# PowerManagement.net
KiCad netlist of a schematic drawn in Altium Designer
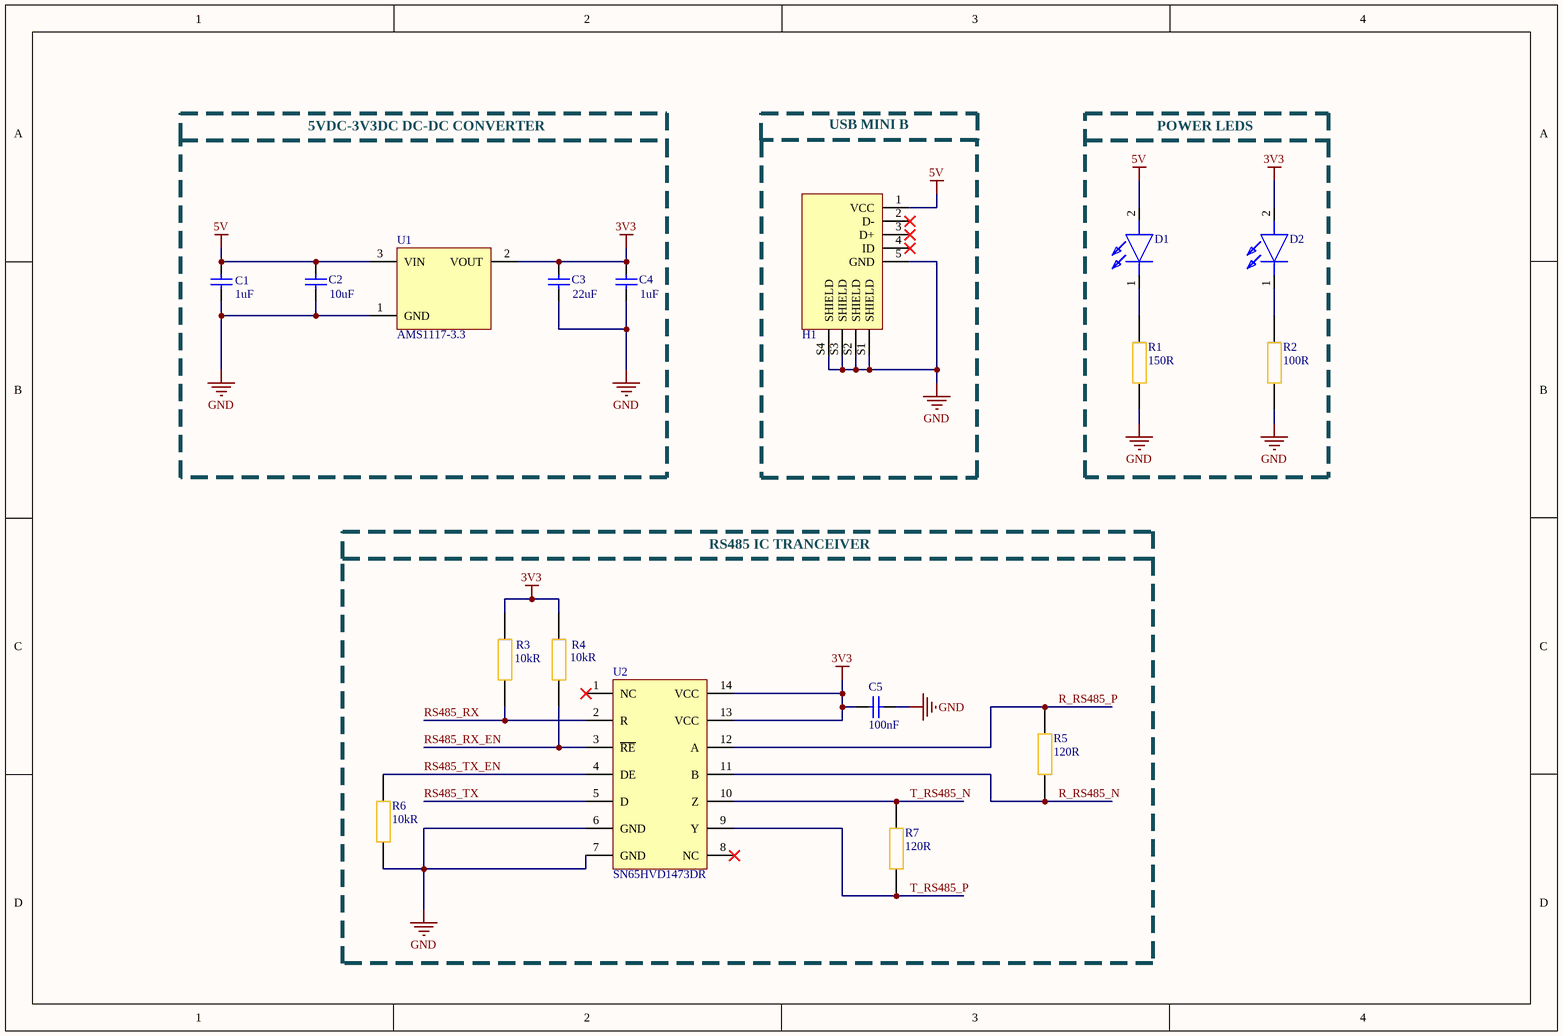
[diagram p0: PowerManagement.SchDoc]

(export (version "E")
  (design (tool "Eeschema 10.0.6"))
  (components
    (comp (ref "C1")
      (value "1uF")
      (footprint "WCAP-CSGP_0603_L1.6W0.8H0.8_Reflow")
      (description "WCAP-CSGP Multilayer Ceramic Chip Capacitor, General Purpose, size 0603, X5R, 1µF, 10VDC")
      (fields
        (field (name "MANUFACTURER PART NUMBER") "885012106010")
        (field (name "MANUFACTURER") "Wurth Elektronik")
        (field (name "CAPACITANCE") "1uF")
      )
      (libsource (lib "WE - Passive Components") (part "Capacitor_Non-Polarized"))
    )
    (comp (ref "C2")
      (value "10uF")
      (footprint "WCAP-CSGP_0603_L1.6W0.8H0.8_Reflow")
      (description "WCAP-CSGP Multilayer Ceramic Chip Capacitor, General Purpose, size 0603, X5R, 10µF, 25VDC")
      (fields
        (field (name "MANUFACTURER PART NUMBER") "885012106031")
        (field (name "MANUFACTURER") "Wurth Elektronik")
        (field (name "CAPACITANCE") "10uF")
      )
      (libsource (lib "WE - Passive Components") (part "Capacitor_Non-Polarized"))
    )
    (comp (ref "C3")
      (value "22uF")
      (footprint "WCAP-CSGP_0805_L2W1.25H1.25")
      (description "WCAP-CSGP Multilayer Ceramic Chip Capacitor, General Purpose, size 0805, X5R, 22µF, 10VDC")
      (fields
        (field (name "MANUFACTURER PART NUMBER") "885012107011")
        (field (name "MANUFACTURER") "Wurth Elektronik")
        (field (name "CAPACITANCE") "22uF")
      )
      (libsource (lib "WE - Passive Components") (part "Capacitor_Non-Polarized"))
    )
    (comp (ref "C4")
      (value "1uF")
      (footprint "WCAP-CSGP_0603_L1.6W0.8H0.8_Reflow")
      (description "WCAP-CSGP Multilayer Ceramic Chip Capacitor, General Purpose, size 0603, X5R, 1µF, 10VDC")
      (fields
        (field (name "MANUFACTURER PART NUMBER") "885012106010")
        (field (name "MANUFACTURER") "Wurth Elektronik")
        (field (name "CAPACITANCE") "1uF")
      )
      (libsource (lib "WE - Passive Components") (part "Capacitor_Non-Polarized"))
    )
    (comp (ref "C5")
      (value "100nF")
      (footprint "WCAP-CSGP_0603_L1.6W0.8H0.8_Reflow")
      (description "WCAP-CSGP Multilayer Ceramic Chip Capacitor, General Purpose, size 0603, X7R, 100nF, 16VDC")
      (fields
        (field (name "MANUFACTURER PART NUMBER") "885012206046")
        (field (name "MANUFACTURER") "Wurth Elektronik")
      )
      (libsource (lib "WE - Passive Components") (part "Capacitor_Non-Polarized"))
    )
    (comp (ref "D1")
      (value "APT1608SGC")
      (footprint "LED GREEN")
      (description "LED GREEN CLEAR 0603 SMD")
      (fields (field (name "MANUFACTURER") "Kingbright") (field (name "DESIGNED BY") "ADAK"))
      (libsource (lib "Integrated_Library5") (part "APT1608SGC"))
    )
    (comp (ref "D2")
      (value "APT1608SGC")
      (footprint "LED GREEN")
      (description "LED GREEN CLEAR 0603 SMD")
      (fields (field (name "MANUFACTURER") "Kingbright") (field (name "DESIGNED BY") "ADAK"))
      (libsource (lib "Integrated_Library5") (part "APT1608SGC"))
    )
    (comp (ref "H1")
      (value "690-005-299-043")
      (footprint "USB")
      (description "CONN RCPT USB2.0 MINI B SMD R/A")
      (fields (field (name "MANUFACTURER") "EDAC") (field (name "DESIGNED BY") "ADAK"))
      (libsource (lib "Integrated_Library5") (part "USB Mini B"))
    )
    (comp (ref "R1")
      (value "RC0603FR-07150RL")
      (footprint "RES 0603")
      (description "RES 150 OHM 1% 1/10W 0603 SMD")
      (fields
        (field (name "MANUFACTURER") "Yageo")
        (field (name "TOLERANCE") "1%")
        (field (name "RESISTANCE") "150R")
        (field (name "DESIGNED BY") "ADAK")
      )
      (libsource (lib "ADAK_Resistors") (part "RES 150 OHM 0603"))
    )
    (comp (ref "R2")
      (value "RC0603FR-13100RL")
      (footprint "RES 0603")
      (description "RES 100 OHM 1% 1/10W 0603 SMD")
      (fields
        (field (name "MANUFACTURER") "Yageo")
        (field (name "TOLERANCE") "1%")
        (field (name "RESISTANCE") "100R")
        (field (name "DESIGNED BY") "ADAK")
      )
      (libsource (lib "ADAK_Resistors") (part "RES 100 OHM 0603"))
    )
    (comp (ref "R3")
      (value "RC0603FR-0710KP")
      (footprint "RES 0603")
      (description "RES 10K OHM 1% 1/10W 0603 SMD")
      (fields
        (field (name "MANUFACTURER") "Yageo")
        (field (name "TOLERANCE") "1%")
        (field (name "RESISTANCE") "10kR")
        (field (name "DESIGNED BY") "ADAK")
      )
      (libsource (lib "ADAK_Resistors") (part "RES 10K OHM 0603"))
    )
    (comp (ref "R4")
      (value "RC0603FR-0710KP")
      (footprint "RES 0603")
      (description "RES 10K OHM 1% 1/10W 0603 SMD")
      (fields
        (field (name "MANUFACTURER") "Yageo")
        (field (name "TOLERANCE") "1%")
        (field (name "RESISTANCE") "10kR")
        (field (name "DESIGNED BY") "ADAK")
      )
      (libsource (lib "ADAK_Resistors") (part "RES 10K OHM 0603"))
    )
    (comp (ref "R5")
      (value "RC0603FR-07120RL")
      (footprint "RES 0603")
      (description "RES 120 OHM 1% 1/10W 0603 SMD")
      (fields
        (field (name "MANUFACTURER") "Yageo")
        (field (name "TOLERANCE") "1%")
        (field (name "RESISTANCE") "120R")
        (field (name "DESIGNED BY") "ADAK")
      )
      (libsource (lib "ADAK_Resistors") (part "RES 120 OHM 0603"))
    )
    (comp (ref "R6")
      (value "RC0603FR-0710KP")
      (footprint "RES 0603")
      (description "RES 10K OHM 1% 1/10W 0603 SMD")
      (fields
        (field (name "MANUFACTURER") "Yageo")
        (field (name "TOLERANCE") "1%")
        (field (name "RESISTANCE") "10kR")
        (field (name "DESIGNED BY") "ADAK")
      )
      (libsource (lib "ADAK_Resistors") (part "RES 10K OHM 0603"))
    )
    (comp (ref "R7")
      (value "RC0603FR-07120RL")
      (footprint "RES 0603")
      (description "RES 120 OHM 1% 1/10W 0603 SMD")
      (fields
        (field (name "MANUFACTURER") "Yageo")
        (field (name "TOLERANCE") "1%")
        (field (name "RESISTANCE") "120R")
        (field (name "DESIGNED BY") "ADAK")
      )
      (libsource (lib "ADAK_Resistors") (part "RES 120 OHM 0603"))
    )
    (comp (ref "U1")
      (value "AMS1117-3.3")
      (footprint "SOT-223")
      (description "Low Dropout Voltage Regulatator SOT-223 1A 3.3V")
      (fields (field (name "DESIGNED BY") "ADAK"))
      (libsource (lib "Integrated_Library5") (part "AMS1117-3.3"))
    )
    (comp (ref "U2")
      (value "SN65HVD1473DR")
      (footprint "14-SOIC")
      (description "IC TRANSCEIVER FULL 1/1 14SOIC")
      (fields (field (name "MANUFACTURER") "Texas Instruments") (field (name "DESIGNED BY") "ADAK"))
      (libsource (lib "Integrated_Library5") (part "SN65HVD1473DR"))
    )
  )
  (nets
    (net (code "1") (name "/RS485_RX") (class "Default")
      (node (ref "R3") (pin "1") (pinfunction "1_1") (pintype "passive"))
      (node (ref "U2") (pin "2") (pinfunction "R_2") (pintype "passive"))
    )
    (net (code "2") (name "/RS485_RX_EN") (class "Default")
      (node (ref "R4") (pin "1") (pinfunction "1_1") (pintype "passive"))
      (node (ref "U2") (pin "3") (pinfunction "~{RE}_3") (pintype "passive"))
    )
    (net (code "3") (name "/RS485_TX") (class "Default")
      (node (ref "U2") (pin "5") (pinfunction "D_5") (pintype "passive"))
    )
    (net (code "4") (name "/RS485_TX_EN") (class "Default")
      (node (ref "R6") (pin "1") (pinfunction "1_1") (pintype "passive"))
      (node (ref "U2") (pin "4") (pinfunction "DE_4") (pintype "passive"))
    )
    (net (code "5") (name "/R_RS485_N") (class "Default")
      (node (ref "R5") (pin "2") (pinfunction "2_2") (pintype "passive"))
      (node (ref "U2") (pin "11") (pinfunction "B_11") (pintype "passive"))
    )
    (net (code "6") (name "/R_RS485_P") (class "Default")
      (node (ref "R5") (pin "1") (pinfunction "1_1") (pintype "passive"))
      (node (ref "U2") (pin "12") (pinfunction "A_12") (pintype "passive"))
    )
    (net (code "7") (name "/T_RS485_N") (class "Default")
      (node (ref "R7") (pin "2") (pinfunction "2_2") (pintype "passive"))
      (node (ref "U2") (pin "10") (pinfunction "Z_10") (pintype "passive"))
    )
    (net (code "8") (name "/T_RS485_P") (class "Default")
      (node (ref "R7") (pin "1") (pinfunction "1_1") (pintype "passive"))
      (node (ref "U2") (pin "9") (pinfunction "Y_9") (pintype "passive"))
    )
    (net (code "9") (name "3V3") (class "Default")
      (node (ref "C3") (pin "2") (pinfunction "2_2") (pintype "passive"))
      (node (ref "C4") (pin "2") (pinfunction "2_2") (pintype "passive"))
      (node (ref "C5") (pin "2") (pinfunction "2_2") (pintype "passive"))
      (node (ref "D2") (pin "2") (pinfunction "A_2") (pintype "passive"))
      (node (ref "R3") (pin "2") (pinfunction "2_2") (pintype "passive"))
      (node (ref "R4") (pin "2") (pinfunction "2_2") (pintype "passive"))
      (node (ref "U1") (pin "2") (pinfunction "VOUT_2") (pintype "passive"))
      (node (ref "U2") (pin "13") (pinfunction "VCC_13") (pintype "passive"))
      (node (ref "U2") (pin "14") (pinfunction "VCC_14") (pintype "passive"))
    )
    (net (code "10") (name "5V") (class "Default")
      (node (ref "C1") (pin "2") (pinfunction "2_2") (pintype "passive"))
      (node (ref "C2") (pin "2") (pinfunction "2_2") (pintype "passive"))
      (node (ref "D1") (pin "2") (pinfunction "A_2") (pintype "passive"))
      (node (ref "H1") (pin "1") (pinfunction "VCC_1") (pintype "passive"))
      (node (ref "U1") (pin "3") (pinfunction "VIN_3") (pintype "passive"))
    )
    (net (code "11") (name "GND") (class "Default")
      (node (ref "C1") (pin "1") (pinfunction "1_1") (pintype "passive"))
      (node (ref "C2") (pin "1") (pinfunction "1_1") (pintype "passive"))
      (node (ref "C3") (pin "1") (pinfunction "1_1") (pintype "passive"))
      (node (ref "C4") (pin "1") (pinfunction "1_1") (pintype "passive"))
      (node (ref "C5") (pin "1") (pinfunction "1_1") (pintype "passive"))
      (node (ref "H1") (pin "5") (pinfunction "GND_5") (pintype "passive"))
      (node (ref "H1") (pin "S1") (pinfunction "SHIELD_S1") (pintype "passive"))
      (node (ref "H1") (pin "S2") (pinfunction "SHIELD_S2") (pintype "passive"))
      (node (ref "H1") (pin "S3") (pinfunction "SHIELD_S3") (pintype "passive"))
      (node (ref "H1") (pin "S4") (pinfunction "SHIELD_S4") (pintype "passive"))
      (node (ref "R1") (pin "1") (pinfunction "1_1") (pintype "passive"))
      (node (ref "R2") (pin "1") (pinfunction "1_1") (pintype "passive"))
      (node (ref "R6") (pin "2") (pinfunction "2_2") (pintype "passive"))
      (node (ref "U1") (pin "1") (pinfunction "GND_1") (pintype "passive"))
      (node (ref "U2") (pin "6") (pinfunction "GND_6") (pintype "passive"))
      (node (ref "U2") (pin "7") (pinfunction "GND_7") (pintype "passive"))
    )
    (net (code "12") (name "Net-(D1-K)") (class "Default")
      (node (ref "D1") (pin "1") (pinfunction "K_1") (pintype "passive"))
      (node (ref "R1") (pin "2") (pinfunction "2_2") (pintype "passive"))
    )
    (net (code "13") (name "Net-(D2-K)") (class "Default")
      (node (ref "D2") (pin "1") (pinfunction "K_1") (pintype "passive"))
      (node (ref "R2") (pin "2") (pinfunction "2_2") (pintype "passive"))
    )
    (net (code "14") (name "unconnected-(H1-D+-Pad3)") (class "Default")
      (node (ref "H1") (pin "3") (pinfunction "D+_3") (pintype "passive+no_connect"))
    )
    (net (code "15") (name "unconnected-(H1-D--Pad2)") (class "Default")
      (node (ref "H1") (pin "2") (pinfunction "D-_2") (pintype "passive+no_connect"))
    )
    (net (code "16") (name "unconnected-(H1-ID-Pad4)") (class "Default")
      (node (ref "H1") (pin "4") (pinfunction "ID_4") (pintype "passive+no_connect"))
    )
    (net (code "17") (name "unconnected-(U2-NC-Pad1)") (class "Default")
      (node (ref "U2") (pin "1") (pinfunction "NC_1") (pintype "passive+no_connect"))
    )
    (net (code "18") (name "unconnected-(U2-NC-Pad8)") (class "Default")
      (node (ref "U2") (pin "8") (pinfunction "NC_8") (pintype "passive+no_connect"))
    )
  )
)
